# Master.net
KiCad netlist of a schematic drawn in Altium Designer
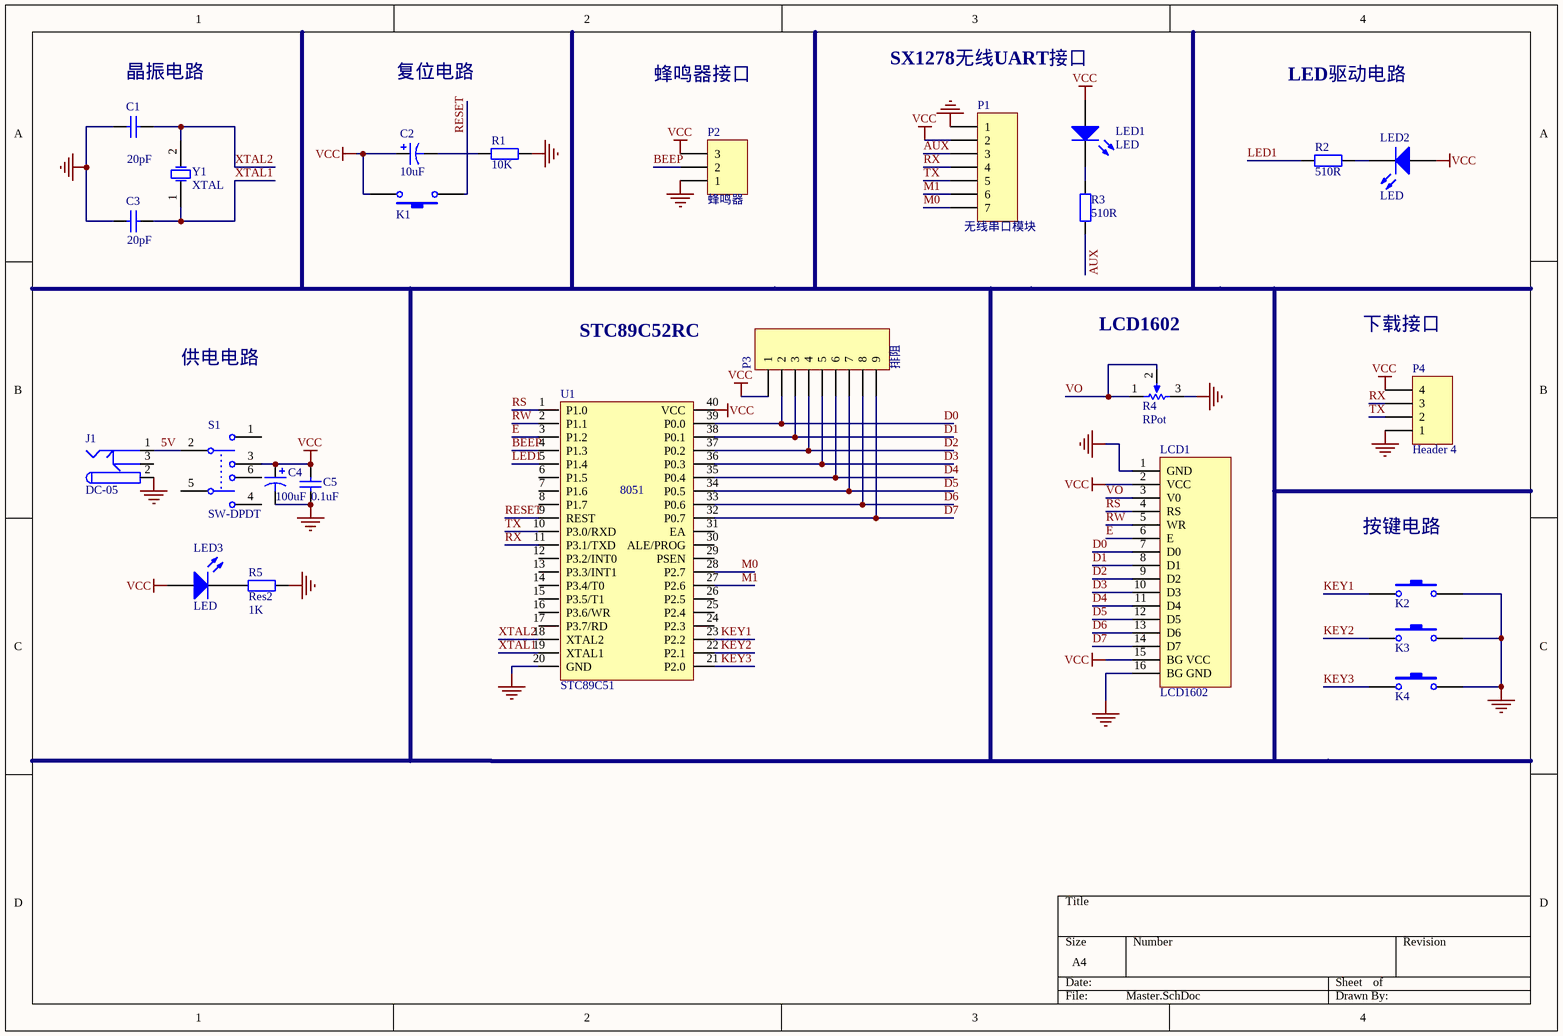
[diagram p0: Master.SchDoc]

(export (version "E")
  (design (tool "Eeschema 10.0.6"))
  (components
    (comp (ref "C1")
      (value "20pF")
      (footprint "RAD-0.1")
      (description "Capacitor")
      (fields (field (name "Comment") "Cap") (field (name "PUBLISHER") "Altium Limited"))
      (libsource (lib "Miscellaneous Devices") (part "Cap"))
    )
    (comp (ref "C2")
      (value "10uF")
      (footprint "RB.1/.2")
      (description "Polarized Capacitor (Radial)")
      (fields (field (name "Comment") "Cap Pol1") (field (name "PUBLISHER") "Altium Limited"))
      (libsource (lib "Miscellaneous Devices") (part "Cap Pol1"))
    )
    (comp (ref "C3")
      (value "20pF")
      (footprint "RAD-0.1")
      (description "Capacitor")
      (fields (field (name "Comment") "Cap") (field (name "PUBLISHER") "Altium Limited"))
      (libsource (lib "Miscellaneous Devices") (part "Cap"))
    )
    (comp (ref "C4")
      (value "100uF")
      (footprint "RB.1/.2")
      (description "Polarized Capacitor (Radial)")
      (fields (field (name "Comment") "Cap Pol1") (field (name "PUBLISHER") "Altium Limited"))
      (libsource (lib "Miscellaneous Devices") (part "Cap Pol1"))
    )
    (comp (ref "C5")
      (value "0.1uF")
      (footprint "RAD-0.1")
      (description "Capacitor")
      (fields (field (name "Comment") "Cap") (field (name "PUBLISHER") "Altium Limited"))
      (libsource (lib "Miscellaneous Devices") (part "Cap"))
    )
    (comp (ref "J1") (value "DC-05") (footprint "DC-05") (libsource (lib "My library") (part "DC-05")))
    (comp (ref "K1") (value "四脚按键") (footprint "四脚按键") (libsource (lib "My library") (part "四脚按键")))
    (comp (ref "K2") (value "四脚按键") (footprint "四脚按键") (libsource (lib "My library") (part "四脚按键")))
    (comp (ref "K3") (value "四脚按键") (footprint "四脚按键") (libsource (lib "My library") (part "四脚按键")))
    (comp (ref "K4") (value "四脚按键") (footprint "四脚按键") (libsource (lib "My library") (part "四脚按键")))
    (comp (ref "LCD1")
      (value "LCD1602")
      (footprint "LCD1602")
      (libsource (lib "My library") (part "LCD1602"))
    )
    (comp (ref "LED1") (value "LED") (footprint "LED") (libsource (lib "My library") (part "LED")))
    (comp (ref "LED2") (value "LED") (footprint "LED") (libsource (lib "My library") (part "LED")))
    (comp (ref "LED3") (value "LED") (footprint "LED") (libsource (lib "My library") (part "LED")))
    (comp (ref "P1")
      (value "无线串口模块")
      (footprint "AS32-TTL-100")
      (description "Header, 7-Pin")
      (fields (field (name "PUBLISHER") "Altium Limited"))
      (libsource (lib "Miscellaneous Connectors") (part "Header 7"))
    )
    (comp (ref "P2")
      (value "蜂鸣器")
      (footprint "HDR1X3")
      (description "Header, 3-Pin")
      (fields (field (name "PUBLISHER") "Altium Limited"))
      (libsource (lib "Miscellaneous Connectors") (part "Header 3"))
    )
    (comp (ref "P3")
      (value "排阻")
      (footprint "HDR1X9")
      (description "Header, 9-Pin")
      (fields (field (name "PUBLISHER") "Altium Limited"))
      (libsource (lib "Miscellaneous Connectors") (part "Header 9"))
    )
    (comp (ref "P4")
      (value "Header 4")
      (footprint "HDR1X4")
      (description "Header, 4-Pin")
      (fields (field (name "PUBLISHER") "Altium Limited"))
      (libsource (lib "Miscellaneous Connectors") (part "Header 4"))
    )
    (comp (ref "R1")
      (value "10K")
      (footprint "AXIAL-0.4")
      (description "Resistor")
      (fields (field (name "Comment") "Res2") (field (name "PUBLISHER") "Altium Limited"))
      (libsource (lib "") (part "Res2_2"))
    )
    (comp (ref "R2")
      (value "510R")
      (footprint "AXIAL-0.4")
      (description "Resistor")
      (fields (field (name "Comment") "Res2") (field (name "PUBLISHER") "Altium Limited"))
      (libsource (lib "Miscellaneous Devices") (part "Res2"))
    )
    (comp (ref "R3")
      (value "510R")
      (footprint "AXIAL-0.4")
      (description "Resistor")
      (fields (field (name "Comment") "Res2") (field (name "PUBLISHER") "Altium Limited"))
      (libsource (lib "") (part "Res2_1"))
    )
    (comp (ref "R4") (value "RPot") (footprint "RPot") (libsource (lib "My library") (part "RPOT")))
    (comp (ref "R5")
      (value "Res2")
      (footprint "AXIAL-0.4")
      (description "Resistor")
      (fields (field (name "ALTIUM_VALUE") "1K") (field (name "PUBLISHER") "Altium Limited"))
      (libsource (lib "Miscellaneous Devices") (part "Res2"))
    )
    (comp (ref "S1")
      (value "SW-DPDT")
      (footprint "SWITCH_B1")
      (description "单刀双掷开关")
      (fields (field (name "PUBLISHER") "Altium Limited"))
      (libsource (lib "Fszhang") (part "SW-DPDT"))
    )
    (comp (ref "U1") (value "STC89C51") (footprint "DIP-40") (libsource (lib "My library") (part "STC89C51")))
    (comp (ref "Y1")
      (value "XTAL")
      (footprint "XTAL_US")
      (description "Crystal Oscillator")
      (fields (field (name "PUBLISHER") "Altium Limited"))
      (libsource (lib "Miscellaneous Devices") (part "XTAL"))
    )
  )
  (nets
    (net (code "1") (name "/5V") (class "Default")
      (node (ref "J1") (pin "1") (pinfunction "1_1") (pintype "passive"))
      (node (ref "S1") (pin "2") (pinfunction "2_2") (pintype "passive"))
    )
    (net (code "2") (name "/AUX") (class "Default")
      (node (ref "P1") (pin "3") (pinfunction "3_3") (pintype "passive"))
      (node (ref "R3") (pin "1") (pinfunction "1_1") (pintype "passive"))
    )
    (net (code "3") (name "/BEEP") (class "Default")
      (node (ref "P2") (pin "2") (pinfunction "2_2") (pintype "passive"))
      (node (ref "U1") (pin "4") (pinfunction "P1.3_4") (pintype "passive"))
    )
    (net (code "4") (name "/D0") (class "Default")
      (node (ref "LCD1") (pin "7") (pinfunction "D0_7") (pintype "power_in"))
      (node (ref "P3") (pin "2") (pinfunction "2_2") (pintype "passive"))
      (node (ref "U1") (pin "39") (pinfunction "P0.0_39") (pintype "passive"))
    )
    (net (code "5") (name "/D1") (class "Default")
      (node (ref "LCD1") (pin "8") (pinfunction "D1_8") (pintype "power_in"))
      (node (ref "P3") (pin "3") (pinfunction "3_3") (pintype "passive"))
      (node (ref "U1") (pin "38") (pinfunction "P0.1_38") (pintype "passive"))
    )
    (net (code "6") (name "/D2") (class "Default")
      (node (ref "LCD1") (pin "9") (pinfunction "D2_9") (pintype "power_in"))
      (node (ref "P3") (pin "4") (pinfunction "4_4") (pintype "passive"))
      (node (ref "U1") (pin "37") (pinfunction "P0.2_37") (pintype "passive"))
    )
    (net (code "7") (name "/D3") (class "Default")
      (node (ref "LCD1") (pin "10") (pinfunction "D3_10") (pintype "power_in"))
      (node (ref "P3") (pin "5") (pinfunction "5_5") (pintype "passive"))
      (node (ref "U1") (pin "36") (pinfunction "P0.3_36") (pintype "passive"))
    )
    (net (code "8") (name "/D4") (class "Default")
      (node (ref "LCD1") (pin "11") (pinfunction "D4_11") (pintype "power_in"))
      (node (ref "P3") (pin "6") (pinfunction "6_6") (pintype "passive"))
      (node (ref "U1") (pin "35") (pinfunction "P0.4_35") (pintype "passive"))
    )
    (net (code "9") (name "/D5") (class "Default")
      (node (ref "LCD1") (pin "12") (pinfunction "D5_12") (pintype "power_in"))
      (node (ref "P3") (pin "7") (pinfunction "7_7") (pintype "passive"))
      (node (ref "U1") (pin "34") (pinfunction "P0.5_34") (pintype "passive"))
    )
    (net (code "10") (name "/D6") (class "Default")
      (node (ref "LCD1") (pin "13") (pinfunction "D6_13") (pintype "power_in"))
      (node (ref "P3") (pin "8") (pinfunction "8_8") (pintype "passive"))
      (node (ref "U1") (pin "33") (pinfunction "P0.6_33") (pintype "passive"))
    )
    (net (code "11") (name "/D7") (class "Default")
      (node (ref "LCD1") (pin "14") (pinfunction "D7_14") (pintype "power_in"))
      (node (ref "P3") (pin "9") (pinfunction "9_9") (pintype "passive"))
      (node (ref "U1") (pin "32") (pinfunction "P0.7_32") (pintype "passive"))
    )
    (net (code "12") (name "/E") (class "Default")
      (node (ref "LCD1") (pin "6") (pinfunction "E_6") (pintype "power_in"))
      (node (ref "U1") (pin "3") (pinfunction "P1.2_3") (pintype "passive"))
    )
    (net (code "13") (name "/KEY1") (class "Default")
      (node (ref "K2") (pin "2") (pinfunction "2_2") (pintype "passive"))
      (node (ref "U1") (pin "23") (pinfunction "P2.2_23") (pintype "passive"))
    )
    (net (code "14") (name "/KEY2") (class "Default")
      (node (ref "K3") (pin "2") (pinfunction "2_2") (pintype "passive"))
      (node (ref "U1") (pin "22") (pinfunction "P2.1_22") (pintype "passive"))
    )
    (net (code "15") (name "/KEY3") (class "Default")
      (node (ref "K4") (pin "2") (pinfunction "2_2") (pintype "passive"))
      (node (ref "U1") (pin "21") (pinfunction "P2.0_21") (pintype "passive"))
    )
    (net (code "16") (name "/LED1") (class "Default")
      (node (ref "R2") (pin "1") (pinfunction "1_1") (pintype "passive"))
      (node (ref "U1") (pin "5") (pinfunction "P1.4_5") (pintype "passive"))
    )
    (net (code "17") (name "/M0") (class "Default")
      (node (ref "P1") (pin "7") (pinfunction "7_7") (pintype "passive"))
      (node (ref "U1") (pin "28") (pinfunction "P2.7_28") (pintype "passive"))
    )
    (net (code "18") (name "/M1") (class "Default")
      (node (ref "P1") (pin "6") (pinfunction "6_6") (pintype "passive"))
      (node (ref "U1") (pin "27") (pinfunction "P2.6_27") (pintype "passive"))
    )
    (net (code "19") (name "/RESET") (class "Default")
      (node (ref "K1") (pin "2") (pinfunction "2_2") (pintype "passive"))
      (node (ref "U1") (pin "9") (pinfunction "REST_9") (pintype "passive"))
    )
    (net (code "20") (name "/RS") (class "Default")
      (node (ref "LCD1") (pin "4") (pinfunction "RS_4") (pintype "power_in"))
      (node (ref "U1") (pin "1") (pinfunction "P1.0_1") (pintype "passive"))
    )
    (net (code "21") (name "/RW") (class "Default")
      (node (ref "LCD1") (pin "5") (pinfunction "WR_5") (pintype "power_in"))
      (node (ref "U1") (pin "2") (pinfunction "P1.1_2") (pintype "passive"))
    )
    (net (code "22") (name "/RX") (class "Default")
      (node (ref "P1") (pin "4") (pinfunction "4_4") (pintype "passive"))
      (node (ref "P4") (pin "3") (pinfunction "3_3") (pintype "passive"))
      (node (ref "U1") (pin "11") (pinfunction "P3.1/TXD_11") (pintype "passive"))
    )
    (net (code "23") (name "/TX") (class "Default")
      (node (ref "P1") (pin "5") (pinfunction "5_5") (pintype "passive"))
      (node (ref "P4") (pin "2") (pinfunction "2_2") (pintype "passive"))
      (node (ref "U1") (pin "10") (pinfunction "P3.0/RXD_10") (pintype "passive"))
    )
    (net (code "24") (name "/VO") (class "Default")
      (node (ref "LCD1") (pin "3") (pinfunction "V0_3") (pintype "power_in"))
      (node (ref "R4") (pin "1") (pinfunction "1_1") (pintype "passive"))
      (node (ref "R4") (pin "2") (pinfunction "2_2") (pintype "passive"))
    )
    (net (code "25") (name "/XTAL1") (class "Default")
      (node (ref "C3") (pin "1") (pinfunction "1_1") (pintype "passive"))
      (node (ref "U1") (pin "19") (pinfunction "XTAL1_19") (pintype "passive"))
      (node (ref "Y1") (pin "1") (pinfunction "OSC1_1") (pintype "passive"))
    )
    (net (code "26") (name "/XTAL2") (class "Default")
      (node (ref "C1") (pin "1") (pinfunction "1_1") (pintype "passive"))
      (node (ref "U1") (pin "18") (pinfunction "XTAL2_18") (pintype "passive"))
      (node (ref "Y1") (pin "2") (pinfunction "OSC2_2") (pintype "passive"))
    )
    (net (code "27") (name "GND") (class "Default")
      (node (ref "C1") (pin "2") (pinfunction "2_2") (pintype "passive"))
      (node (ref "C3") (pin "2") (pinfunction "2_2") (pintype "passive"))
      (node (ref "C4") (pin "2") (pinfunction "2_2") (pintype "passive"))
      (node (ref "C5") (pin "1") (pinfunction "1_1") (pintype "passive"))
      (node (ref "J1") (pin "2") (pinfunction "2_2") (pintype "passive"))
      (node (ref "K2") (pin "1") (pinfunction "1_1") (pintype "passive"))
      (node (ref "K3") (pin "1") (pinfunction "1_1") (pintype "passive"))
      (node (ref "K4") (pin "1") (pinfunction "1_1") (pintype "passive"))
      (node (ref "LCD1") (pin "1") (pinfunction "GND_1") (pintype "power_in"))
      (node (ref "LCD1") (pin "16") (pinfunction "BG_GND_16") (pintype "power_in"))
      (node (ref "P1") (pin "1") (pinfunction "1_1") (pintype "passive"))
      (node (ref "P2") (pin "1") (pinfunction "1_1") (pintype "passive"))
      (node (ref "P4") (pin "1") (pinfunction "1_1") (pintype "passive"))
      (node (ref "R1") (pin "1") (pinfunction "1_1") (pintype "passive"))
      (node (ref "R4") (pin "3") (pinfunction "3_3") (pintype "passive"))
      (node (ref "R5") (pin "2") (pinfunction "2_2") (pintype "passive"))
      (node (ref "U1") (pin "20") (pinfunction "GND_20") (pintype "passive"))
    )
    (net (code "28") (name "Net-(C2-Pad2)") (class "Default")
      (node (ref "C2") (pin "2") (pinfunction "2_2") (pintype "passive"))
      (node (ref "R1") (pin "2") (pinfunction "2_2") (pintype "passive"))
    )
    (net (code "29") (name "Net-(LED1-Pad2)") (class "Default")
      (node (ref "LED1") (pin "2") (pinfunction "2_2") (pintype "passive"))
      (node (ref "R3") (pin "2") (pinfunction "2_2") (pintype "passive"))
    )
    (net (code "30") (name "Net-(LED2-Pad2)") (class "Default")
      (node (ref "LED2") (pin "2") (pinfunction "2_2") (pintype "passive"))
      (node (ref "R2") (pin "2") (pinfunction "2_2") (pintype "passive"))
    )
    (net (code "31") (name "Net-(LED3-Pad2)") (class "Default")
      (node (ref "LED3") (pin "2") (pinfunction "2_2") (pintype "passive"))
      (node (ref "R5") (pin "1") (pinfunction "1_1") (pintype "passive"))
    )
    (net (code "32") (name "VCC") (class "Default")
      (node (ref "C2") (pin "1") (pinfunction "1_1") (pintype "passive"))
      (node (ref "C4") (pin "1") (pinfunction "1_1") (pintype "passive"))
      (node (ref "C5") (pin "2") (pinfunction "2_2") (pintype "passive"))
      (node (ref "K1") (pin "1") (pinfunction "1_1") (pintype "passive"))
      (node (ref "LCD1") (pin "15") (pinfunction "BG_VCC_15") (pintype "power_in"))
      (node (ref "LCD1") (pin "2") (pinfunction "VCC_2") (pintype "power_in"))
      (node (ref "LED1") (pin "1") (pinfunction "1_1") (pintype "passive"))
      (node (ref "LED2") (pin "1") (pinfunction "1_1") (pintype "passive"))
      (node (ref "LED3") (pin "1") (pinfunction "1_1") (pintype "passive"))
      (node (ref "P1") (pin "2") (pinfunction "2_2") (pintype "passive"))
      (node (ref "P2") (pin "3") (pinfunction "3_3") (pintype "passive"))
      (node (ref "P3") (pin "1") (pinfunction "1_1") (pintype "passive"))
      (node (ref "P4") (pin "4") (pinfunction "4_4") (pintype "passive"))
      (node (ref "S1") (pin "3") (pinfunction "3_3") (pintype "passive"))
      (node (ref "U1") (pin "40") (pinfunction "VCC_40") (pintype "passive"))
    )
    (net (code "33") (name "unconnected-(J1-Pad3)") (class "Default")
      (node (ref "J1") (pin "3") (pinfunction "3_3") (pintype "passive"))
    )
    (net (code "34") (name "unconnected-(S1-Pad1)") (class "Default")
      (node (ref "S1") (pin "1") (pinfunction "1_1") (pintype "passive"))
    )
    (net (code "35") (name "unconnected-(S1-Pad4)") (class "Default")
      (node (ref "S1") (pin "4") (pinfunction "4_4") (pintype "passive"))
    )
    (net (code "36") (name "unconnected-(S1-Pad5)") (class "Default")
      (node (ref "S1") (pin "5") (pinfunction "5_5") (pintype "passive"))
    )
    (net (code "37") (name "unconnected-(S1-Pad6)") (class "Default")
      (node (ref "S1") (pin "6") (pinfunction "6_6") (pintype "passive"))
    )
    (net (code "38") (name "unconnected-(U1-ALE{slash}PROG-Pad30)") (class "Default")
      (node (ref "U1") (pin "30") (pinfunction "ALE/PROG_30") (pintype "passive"))
    )
    (net (code "39") (name "unconnected-(U1-EA-Pad31)") (class "Default")
      (node (ref "U1") (pin "31") (pinfunction "EA_31") (pintype "passive"))
    )
    (net (code "40") (name "unconnected-(U1-P1.5-Pad6)") (class "Default")
      (node (ref "U1") (pin "6") (pinfunction "P1.5_6") (pintype "passive"))
    )
    (net (code "41") (name "unconnected-(U1-P1.6-Pad7)") (class "Default")
      (node (ref "U1") (pin "7") (pinfunction "P1.6_7") (pintype "passive"))
    )
    (net (code "42") (name "unconnected-(U1-P1.7-Pad8)") (class "Default")
      (node (ref "U1") (pin "8") (pinfunction "P1.7_8") (pintype "passive"))
    )
    (net (code "43") (name "unconnected-(U1-P2.3-Pad24)") (class "Default")
      (node (ref "U1") (pin "24") (pinfunction "P2.3_24") (pintype "passive"))
    )
    (net (code "44") (name "unconnected-(U1-P2.4-Pad25)") (class "Default")
      (node (ref "U1") (pin "25") (pinfunction "P2.4_25") (pintype "passive"))
    )
    (net (code "45") (name "unconnected-(U1-P2.5-Pad26)") (class "Default")
      (node (ref "U1") (pin "26") (pinfunction "P2.5_26") (pintype "passive"))
    )
    (net (code "46") (name "unconnected-(U1-P3.2{slash}INT0-Pad12)") (class "Default")
      (node (ref "U1") (pin "12") (pinfunction "P3.2/INT0_12") (pintype "passive"))
    )
    (net (code "47") (name "unconnected-(U1-P3.3{slash}INT1-Pad13)") (class "Default")
      (node (ref "U1") (pin "13") (pinfunction "P3.3/INT1_13") (pintype "passive"))
    )
    (net (code "48") (name "unconnected-(U1-P3.4{slash}T0-Pad14)") (class "Default")
      (node (ref "U1") (pin "14") (pinfunction "P3.4/T0_14") (pintype "passive"))
    )
    (net (code "49") (name "unconnected-(U1-P3.5{slash}T1-Pad15)") (class "Default")
      (node (ref "U1") (pin "15") (pinfunction "P3.5/T1_15") (pintype "passive"))
    )
    (net (code "50") (name "unconnected-(U1-P3.6{slash}WR-Pad16)") (class "Default")
      (node (ref "U1") (pin "16") (pinfunction "P3.6/WR_16") (pintype "passive"))
    )
    (net (code "51") (name "unconnected-(U1-P3.7{slash}RD-Pad17)") (class "Default")
      (node (ref "U1") (pin "17") (pinfunction "P3.7/RD_17") (pintype "passive"))
    )
    (net (code "52") (name "unconnected-(U1-PSEN-Pad29)") (class "Default")
      (node (ref "U1") (pin "29") (pinfunction "PSEN_29") (pintype "passive"))
    )
  )
)
